# pi-camera-frame.net
KiCad netlist of a schematic drawn in EAGLE
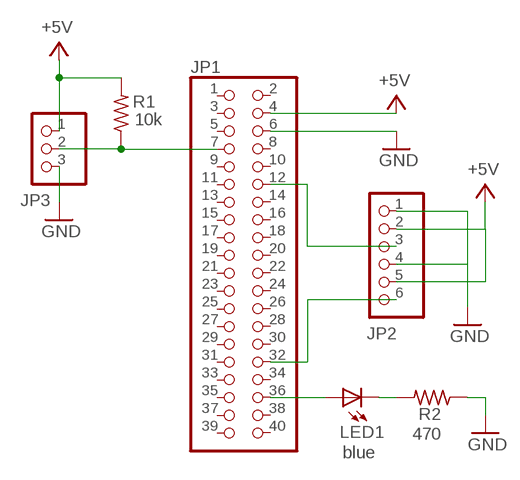
[diagram p0: schematic, sheet 1]

(export (version "E")
  (design (tool "Eeschema 10.0.6"))
  (components
    (comp (ref "JP1")
      (value "PINHD-2X20")
      (footprint "eagle-import:2X20")
      (libsource (lib "eagle-import") (part "PINHD-2X20"))
    )
    (comp (ref "JP2")
      (value "PINHD-1X6")
      (footprint "eagle-import:1X06")
      (libsource (lib "eagle-import") (part "PINHD-1X6"))
    )
    (comp (ref "JP3")
      (value "PINHD-1X3")
      (footprint "eagle-import:1X03")
      (libsource (lib "eagle-import") (part "PINHD-1X3"))
    )
    (comp (ref "LED1")
      (value "blue")
      (footprint "eagle-import:CHIP-LED0603")
      (libsource (lib "eagle-import") (part "LEDCHIP-LED0603"))
    )
    (comp (ref "R1")
      (value "10k")
      (footprint "eagle-import:R0805")
      (libsource (lib "eagle-import") (part "R-US_R0805"))
    )
    (comp (ref "R2")
      (value "470")
      (footprint "eagle-import:R0805")
      (libsource (lib "eagle-import") (part "R-US_R0805"))
    )
  )
  (nets
    (net (code "1") (name "+5V") (class "Default")
      (node (ref "JP1") (pin "4") (pinfunction "4_4") (pintype "passive"))
      (node (ref "JP2") (pin "2") (pinfunction "2_2") (pintype "passive"))
      (node (ref "JP2") (pin "5") (pinfunction "5_5") (pintype "passive"))
      (node (ref "JP3") (pin "1") (pinfunction "1_1") (pintype "passive"))
      (node (ref "R1") (pin "2") (pinfunction "2_2") (pintype "passive"))
    )
    (net (code "2") (name "GND") (class "Default")
      (node (ref "JP1") (pin "6") (pinfunction "6_6") (pintype "passive"))
      (node (ref "JP2") (pin "1") (pinfunction "1_1") (pintype "passive"))
      (node (ref "JP2") (pin "4") (pinfunction "4_4") (pintype "passive"))
      (node (ref "JP3") (pin "3") (pinfunction "3_3") (pintype "passive"))
      (node (ref "R2") (pin "1") (pinfunction "1_1") (pintype "passive"))
    )
    (net (code "3") (name "Net-(JP1-Pad7)") (class "Default")
      (node (ref "JP1") (pin "7") (pinfunction "7_7") (pintype "passive"))
      (node (ref "JP3") (pin "2") (pinfunction "2_2") (pintype "passive"))
      (node (ref "R1") (pin "1") (pinfunction "1_1") (pintype "passive"))
    )
    (net (code "4") (name "Net-(JP1-Pad12)") (class "Default")
      (node (ref "JP1") (pin "12") (pinfunction "12_12") (pintype "passive"))
      (node (ref "JP2") (pin "3") (pinfunction "3_3") (pintype "passive"))
    )
    (net (code "5") (name "Net-(JP1-Pad32)") (class "Default")
      (node (ref "JP1") (pin "32") (pinfunction "32_32") (pintype "passive"))
      (node (ref "JP2") (pin "6") (pinfunction "6_6") (pintype "passive"))
    )
    (net (code "6") (name "Net-(JP1-Pad36)") (class "Default")
      (node (ref "JP1") (pin "36") (pinfunction "36_36") (pintype "passive"))
      (node (ref "LED1") (pin "A") (pinfunction "A_A") (pintype "passive"))
    )
    (net (code "7") (name "Net-(LED1-PadC)") (class "Default")
      (node (ref "LED1") (pin "C") (pinfunction "C_C") (pintype "passive"))
      (node (ref "R2") (pin "2") (pinfunction "2_2") (pintype "passive"))
    )
    (net (code "8") (name "unconnected-(JP1-Pad1)") (class "Default")
      (node (ref "JP1") (pin "1") (pinfunction "1_1") (pintype "passive"))
    )
    (net (code "9") (name "unconnected-(JP1-Pad2)") (class "Default")
      (node (ref "JP1") (pin "2") (pinfunction "2_2") (pintype "passive"))
    )
    (net (code "10") (name "unconnected-(JP1-Pad3)") (class "Default")
      (node (ref "JP1") (pin "3") (pinfunction "3_3") (pintype "passive"))
    )
    (net (code "11") (name "unconnected-(JP1-Pad5)") (class "Default")
      (node (ref "JP1") (pin "5") (pinfunction "5_5") (pintype "passive"))
    )
    (net (code "12") (name "unconnected-(JP1-Pad8)") (class "Default")
      (node (ref "JP1") (pin "8") (pinfunction "8_8") (pintype "passive"))
    )
    (net (code "13") (name "unconnected-(JP1-Pad9)") (class "Default")
      (node (ref "JP1") (pin "9") (pinfunction "9_9") (pintype "passive"))
    )
    (net (code "14") (name "unconnected-(JP1-Pad10)") (class "Default")
      (node (ref "JP1") (pin "10") (pinfunction "10_10") (pintype "passive"))
    )
    (net (code "15") (name "unconnected-(JP1-Pad11)") (class "Default")
      (node (ref "JP1") (pin "11") (pinfunction "11_11") (pintype "passive"))
    )
    (net (code "16") (name "unconnected-(JP1-Pad13)") (class "Default")
      (node (ref "JP1") (pin "13") (pinfunction "13_13") (pintype "passive"))
    )
    (net (code "17") (name "unconnected-(JP1-Pad14)") (class "Default")
      (node (ref "JP1") (pin "14") (pinfunction "14_14") (pintype "passive"))
    )
    (net (code "18") (name "unconnected-(JP1-Pad15)") (class "Default")
      (node (ref "JP1") (pin "15") (pinfunction "15_15") (pintype "passive"))
    )
    (net (code "19") (name "unconnected-(JP1-Pad16)") (class "Default")
      (node (ref "JP1") (pin "16") (pinfunction "16_16") (pintype "passive"))
    )
    (net (code "20") (name "unconnected-(JP1-Pad17)") (class "Default")
      (node (ref "JP1") (pin "17") (pinfunction "17_17") (pintype "passive"))
    )
    (net (code "21") (name "unconnected-(JP1-Pad18)") (class "Default")
      (node (ref "JP1") (pin "18") (pinfunction "18_18") (pintype "passive"))
    )
    (net (code "22") (name "unconnected-(JP1-Pad19)") (class "Default")
      (node (ref "JP1") (pin "19") (pinfunction "19_19") (pintype "passive"))
    )
    (net (code "23") (name "unconnected-(JP1-Pad20)") (class "Default")
      (node (ref "JP1") (pin "20") (pinfunction "20_20") (pintype "passive"))
    )
    (net (code "24") (name "unconnected-(JP1-Pad21)") (class "Default")
      (node (ref "JP1") (pin "21") (pinfunction "21_21") (pintype "passive"))
    )
    (net (code "25") (name "unconnected-(JP1-Pad22)") (class "Default")
      (node (ref "JP1") (pin "22") (pinfunction "22_22") (pintype "passive"))
    )
    (net (code "26") (name "unconnected-(JP1-Pad23)") (class "Default")
      (node (ref "JP1") (pin "23") (pinfunction "23_23") (pintype "passive"))
    )
    (net (code "27") (name "unconnected-(JP1-Pad24)") (class "Default")
      (node (ref "JP1") (pin "24") (pinfunction "24_24") (pintype "passive"))
    )
    (net (code "28") (name "unconnected-(JP1-Pad25)") (class "Default")
      (node (ref "JP1") (pin "25") (pinfunction "25_25") (pintype "passive"))
    )
    (net (code "29") (name "unconnected-(JP1-Pad26)") (class "Default")
      (node (ref "JP1") (pin "26") (pinfunction "26_26") (pintype "passive"))
    )
    (net (code "30") (name "unconnected-(JP1-Pad27)") (class "Default")
      (node (ref "JP1") (pin "27") (pinfunction "27_27") (pintype "passive"))
    )
    (net (code "31") (name "unconnected-(JP1-Pad28)") (class "Default")
      (node (ref "JP1") (pin "28") (pinfunction "28_28") (pintype "passive"))
    )
    (net (code "32") (name "unconnected-(JP1-Pad29)") (class "Default")
      (node (ref "JP1") (pin "29") (pinfunction "29_29") (pintype "passive"))
    )
    (net (code "33") (name "unconnected-(JP1-Pad30)") (class "Default")
      (node (ref "JP1") (pin "30") (pinfunction "30_30") (pintype "passive"))
    )
    (net (code "34") (name "unconnected-(JP1-Pad31)") (class "Default")
      (node (ref "JP1") (pin "31") (pinfunction "31_31") (pintype "passive"))
    )
    (net (code "35") (name "unconnected-(JP1-Pad33)") (class "Default")
      (node (ref "JP1") (pin "33") (pinfunction "33_33") (pintype "passive"))
    )
    (net (code "36") (name "unconnected-(JP1-Pad34)") (class "Default")
      (node (ref "JP1") (pin "34") (pinfunction "34_34") (pintype "passive"))
    )
    (net (code "37") (name "unconnected-(JP1-Pad35)") (class "Default")
      (node (ref "JP1") (pin "35") (pinfunction "35_35") (pintype "passive"))
    )
    (net (code "38") (name "unconnected-(JP1-Pad37)") (class "Default")
      (node (ref "JP1") (pin "37") (pinfunction "37_37") (pintype "passive"))
    )
    (net (code "39") (name "unconnected-(JP1-Pad38)") (class "Default")
      (node (ref "JP1") (pin "38") (pinfunction "38_38") (pintype "passive"))
    )
    (net (code "40") (name "unconnected-(JP1-Pad39)") (class "Default")
      (node (ref "JP1") (pin "39") (pinfunction "39_39") (pintype "passive"))
    )
    (net (code "41") (name "unconnected-(JP1-Pad40)") (class "Default")
      (node (ref "JP1") (pin "40") (pinfunction "40_40") (pintype "passive"))
    )
  )
)
